# led_capacitor.net
KiCad netlist of a schematic drawn in EAGLE
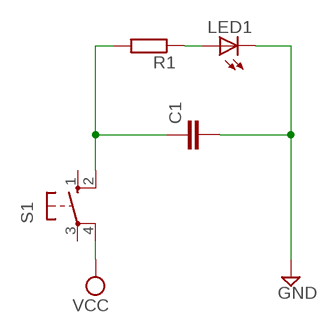
[diagram p0: schematic, sheet 1]

(export (version "E")
  (design (tool "Eeschema 10.0.6"))
  (components
    (comp (ref "C1")
      (value "C5/2.5")
      (footprint "eagle-import:C5B2.5")
      (libsource (lib "eagle-import") (part "C5/2.5"))
    )
    (comp (ref "LED1")
      (value "LED3MM")
      (footprint "eagle-import:LED3MM")
      (libsource (lib "eagle-import") (part "LED3MM"))
    )
    (comp (ref "R1")
      (value "R-EU_0204/5")
      (footprint "eagle-import:0204_5")
      (libsource (lib "eagle-import") (part "R-EU_0204/5"))
    )
    (comp (ref "S1")
      (value "40/XX")
      (footprint "eagle-import:B3F_40XX")
      (libsource (lib "eagle-import") (part "40/XX"))
    )
  )
  (nets
    (net (code "1") (name "GND") (class "Default")
      (node (ref "C1") (pin "2") (pinfunction "2_2") (pintype "passive"))
      (node (ref "LED1") (pin "K") (pinfunction "C_K") (pintype "passive"))
    )
    (net (code "2") (name "Net-(LED1-PadA)") (class "Default")
      (node (ref "LED1") (pin "A") (pinfunction "A_A") (pintype "passive"))
      (node (ref "R1") (pin "1") (pinfunction "1_1") (pintype "passive"))
    )
    (net (code "3") (name "Net-(S1-S1)") (class "Default")
      (node (ref "C1") (pin "1") (pinfunction "1_1") (pintype "passive"))
      (node (ref "R1") (pin "2") (pinfunction "2_2") (pintype "passive"))
      (node (ref "S1") (pin "2") (pinfunction "S1_2") (pintype "passive"))
    )
    (net (code "4") (name "VCC") (class "Default")
      (node (ref "S1") (pin "4") (pinfunction "P1_4") (pintype "passive"))
    )
    (net (code "5") (name "unconnected-(S1-P-Pad3)") (class "Default")
      (node (ref "S1") (pin "3") (pinfunction "P_3") (pintype "passive"))
    )
    (net (code "6") (name "unconnected-(S1-S-Pad1)") (class "Default")
      (node (ref "S1") (pin "1") (pinfunction "S_1") (pintype "passive"))
    )
  )
)
